# Sheet1.net
KiCad netlist of a schematic drawn in Altium Designer
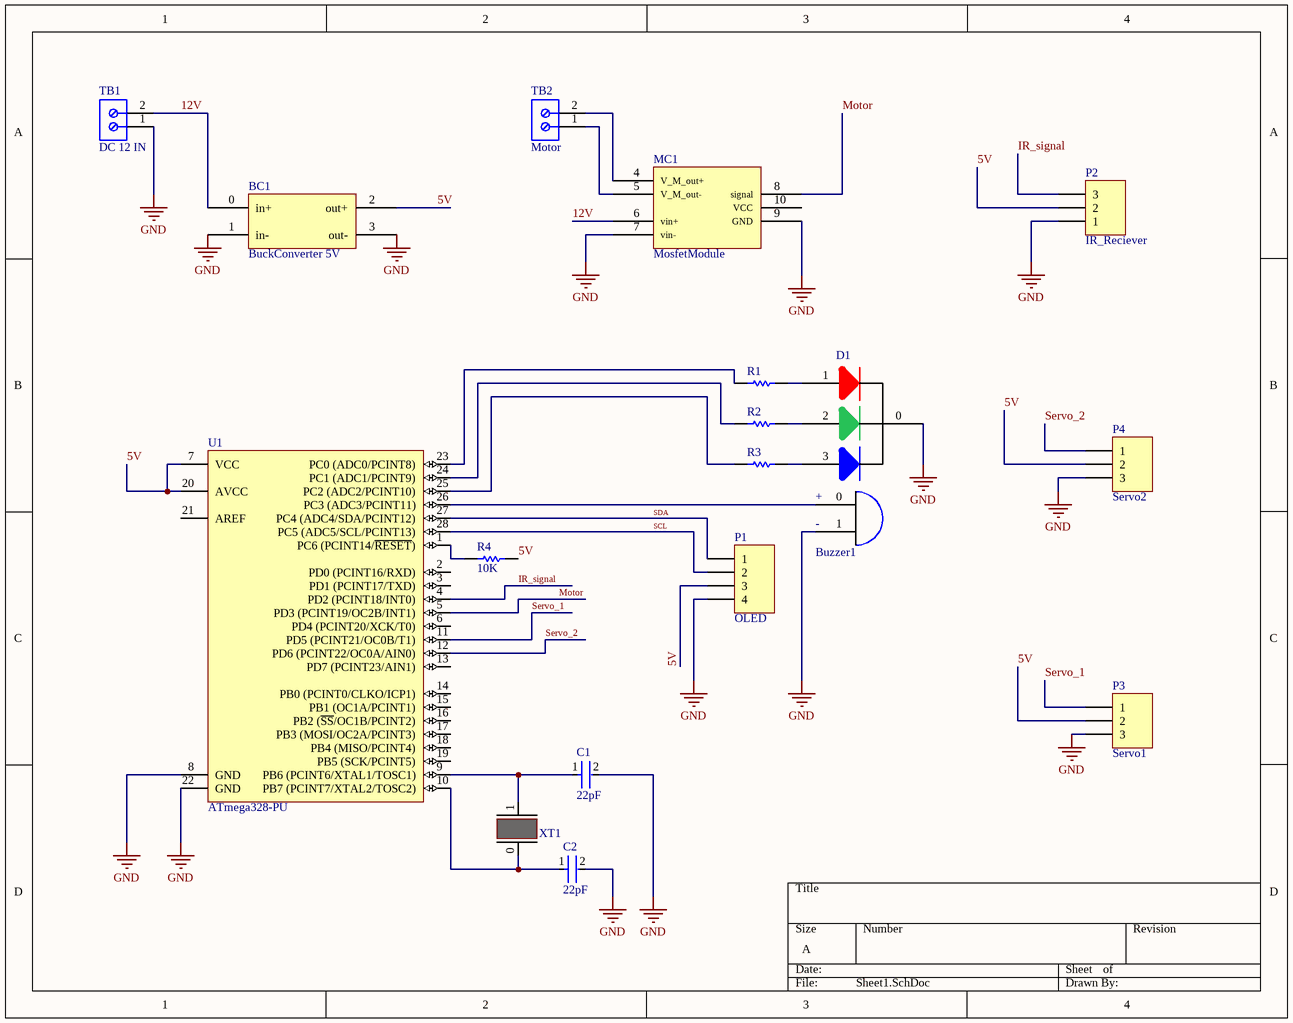
[diagram p0: Sheet1.SchDoc]

(export (version "E")
  (design (tool "Eeschema 10.0.6"))
  (components
    (comp (ref "BC1")
      (value "BuckConverter 5V")
      (footprint "BUCK")
      (libsource (lib "Schlib1") (part "BuckConverter"))
    )
    (comp (ref "Buzzer1") (value "Buzzer") (footprint "Buzzer") (libsource (lib "Schlib1") (part "Buzzer")))
    (comp (ref "C1")
      (value "22pF")
      (footprint "FP-RDE0M1-MFG")
      (description "Ceramic Capacitor 100nF ±10% 50V X7R Radial")
      (fields (field (name "TOLERANCE") "10%"))
      (libsource (lib "Altium Content Vault") (part "b4654b650e69147ec39a6b967a45e02"))
    )
    (comp (ref "C2")
      (value "22pF")
      (footprint "FP-RDE0M1-MFG")
      (description "Ceramic Capacitor 100nF ±10% 50V X7R Radial")
      (fields (field (name "TOLERANCE") "10%"))
      (libsource (lib "Altium Content Vault") (part "b4654b650e69147ec39a6b967a45e02"))
    )
    (comp (ref "D1")
      (value "check foot print and real model")
      (footprint "RGB_LED")
      (libsource (lib "Schlib1") (part "RGB_LED"))
    )
    (comp (ref "MC1")
      (value "MosfetModule")
      (footprint "MosfetMoterDriver")
      (libsource (lib "Schlib1") (part "MosfetModule"))
    )
    (comp (ref "P1")
      (value "OLED")
      (footprint "HDR1X4")
      (description "Header, 4-Pin")
      (fields (field (name "PUBLISHER") "Altium Limited"))
      (libsource (lib "Miscellaneous Connectors") (part "Header 4"))
    )
    (comp (ref "P2")
      (value "IR_Reciever")
      (footprint "HDR1X3")
      (description "Header, 3-Pin")
      (fields (field (name "PUBLISHER") "Altium Limited"))
      (libsource (lib "Miscellaneous Connectors") (part "Header 3"))
    )
    (comp (ref "P3")
      (value "Servo1")
      (footprint "HDR1X3")
      (description "Header, 3-Pin")
      (fields (field (name "PUBLISHER") "Altium Limited"))
      (libsource (lib "") (part "Header 3_1"))
    )
    (comp (ref "P4")
      (value "Servo2")
      (footprint "HDR1X3")
      (description "Header, 3-Pin")
      (fields (field (name "PUBLISHER") "Altium Limited"))
      (libsource (lib "") (part "Header 3_1"))
    )
    (comp (ref "R1")
      (value "MFR-25FBF52-1K")
      (footprint "RESA60-630X240")
      (description "Axial Resistor, 1 KOhm, +/- 1%, 250 mW, -55 to 155 degC, 2-Pin THD, RoHS, Bulk")
      (fields (field (name "TOLERANCE") "1%"))
      (libsource (lib "Altium Content Vault") (part "RES-2"))
    )
    (comp (ref "R2")
      (value "MFR-25FBF52-1K")
      (footprint "RESA60-630X240")
      (description "Axial Resistor, 1 KOhm, +/- 1%, 250 mW, -55 to 155 degC, 2-Pin THD, RoHS, Bulk")
      (fields (field (name "TOLERANCE") "1%"))
      (libsource (lib "Altium Content Vault") (part "RES-2"))
    )
    (comp (ref "R3")
      (value "MFR-25FBF52-1K")
      (footprint "RESA60-630X240")
      (description "Axial Resistor, 1 KOhm, +/- 1%, 250 mW, -55 to 155 degC, 2-Pin THD, RoHS, Bulk")
      (fields (field (name "TOLERANCE") "1%"))
      (libsource (lib "Altium Content Vault") (part "RES-2"))
    )
    (comp (ref "R4")
      (value "10K")
      (footprint "RESA60-630X240")
      (description "Axial Resistor, 1 KOhm, +/- 1%, 250 mW, -55 to 155 degC, 2-Pin THD, RoHS, Bulk")
      (fields (field (name "TOLERANCE") "1%"))
      (libsource (lib "Altium Content Vault") (part "RES-2"))
    )
    (comp (ref "TB1")
      (value "DC 12 IN")
      (footprint "Terminal Block")
      (libsource (lib "Schlib1") (part "Terminal Block"))
    )
    (comp (ref "TB2")
      (value "Motor")
      (footprint "Terminal Block")
      (libsource (lib "Schlib1") (part "Terminal Block"))
    )
    (comp (ref "U1")
      (value "ATmega328-PU")
      (footprint "28P3")
      (libsource (lib "Altium Content Vault") (part "MC-8B-ATM48-IL28"))
    )
    (comp (ref "XT1")
      (value "Crystal Oscillator")
      (footprint "CrystalOscillator")
      (libsource (lib "Schlib1") (part "Crystal Oscillator"))
    )
  )
  (nets
    (net (code "1") (name "/5V") (class "Default")
      (node (ref "BC1") (pin "2") (pinfunction "out+_2") (pintype "passive"))
      (node (ref "P1") (pin "3") (pinfunction "3_3") (pintype "passive"))
      (node (ref "P2") (pin "2") (pinfunction "2_2") (pintype "passive"))
      (node (ref "P3") (pin "2") (pinfunction "2_2") (pintype "passive"))
      (node (ref "P4") (pin "2") (pinfunction "2_2") (pintype "passive"))
      (node (ref "R4") (pin "2") (pinfunction "2_2") (pintype "passive"))
      (node (ref "U1") (pin "20") (pinfunction "AVCC_20") (pintype "power_in"))
      (node (ref "U1") (pin "7") (pinfunction "VCC_7") (pintype "power_in"))
    )
    (net (code "2") (name "/12V") (class "Default")
      (node (ref "BC1") (pin "0") (pinfunction "in+_0") (pintype "passive"))
      (node (ref "MC1") (pin "6") (pinfunction "vin+_6") (pintype "passive"))
      (node (ref "TB1") (pin "2") (pinfunction "2_2") (pintype "passive"))
    )
    (net (code "3") (name "/IR_signal") (class "Default")
      (node (ref "P2") (pin "3") (pinfunction "3_3") (pintype "passive"))
      (node (ref "U1") (pin "4") (pinfunction "PD2_(PCINT18/INT0)_4") (pintype "bidirectional"))
    )
    (net (code "4") (name "/Motor") (class "Default")
      (node (ref "MC1") (pin "8") (pinfunction "signal_8") (pintype "passive"))
      (node (ref "U1") (pin "5") (pinfunction "PD3_(PCINT19/OC2B/INT1)_5") (pintype "bidirectional"))
    )
    (net (code "5") (name "/SCL") (class "Default")
      (node (ref "P1") (pin "2") (pinfunction "2_2") (pintype "passive"))
      (node (ref "U1") (pin "28") (pinfunction "PC5_(ADC5/SCL/PCINT13)_28") (pintype "bidirectional"))
    )
    (net (code "6") (name "/SDA") (class "Default")
      (node (ref "P1") (pin "1") (pinfunction "1_1") (pintype "passive"))
      (node (ref "U1") (pin "27") (pinfunction "PC4_(ADC4/SDA/PCINT12)_27") (pintype "bidirectional"))
    )
    (net (code "7") (name "/Servo_1") (class "Default")
      (node (ref "P3") (pin "1") (pinfunction "1_1") (pintype "passive"))
      (node (ref "U1") (pin "11") (pinfunction "PD5_(PCINT21/OC0B/T1)_11") (pintype "bidirectional"))
    )
    (net (code "8") (name "/Servo_2") (class "Default")
      (node (ref "P4") (pin "1") (pinfunction "1_1") (pintype "passive"))
      (node (ref "U1") (pin "12") (pinfunction "PD6_(PCINT22/OC0A/AIN0)_12") (pintype "bidirectional"))
    )
    (net (code "9") (name "GND") (class "Default")
      (node (ref "BC1") (pin "1") (pinfunction "in-_1") (pintype "passive"))
      (node (ref "BC1") (pin "3") (pinfunction "out-_3") (pintype "passive"))
      (node (ref "Buzzer1") (pin "1") (pinfunction "16_1") (pintype "passive"))
      (node (ref "C1") (pin "2") (pinfunction "2_2") (pintype "passive"))
      (node (ref "C2") (pin "2") (pinfunction "2_2") (pintype "passive"))
      (node (ref "D1") (pin "0") (pinfunction "14_0") (pintype "passive"))
      (node (ref "MC1") (pin "7") (pinfunction "vin-_7") (pintype "passive"))
      (node (ref "MC1") (pin "9") (pinfunction "GND_9") (pintype "passive"))
      (node (ref "P1") (pin "4") (pinfunction "4_4") (pintype "passive"))
      (node (ref "P2") (pin "1") (pinfunction "1_1") (pintype "passive"))
      (node (ref "P3") (pin "3") (pinfunction "3_3") (pintype "passive"))
      (node (ref "P4") (pin "3") (pinfunction "3_3") (pintype "passive"))
      (node (ref "TB1") (pin "1") (pinfunction "1_1") (pintype "passive"))
      (node (ref "U1") (pin "22") (pinfunction "GND_22") (pintype "power_in"))
      (node (ref "U1") (pin "8") (pinfunction "GND_8") (pintype "power_in"))
    )
    (net (code "10") (name "Net-(Buzzer1-15)") (class "Default")
      (node (ref "Buzzer1") (pin "0") (pinfunction "15_0") (pintype "passive"))
      (node (ref "U1") (pin "26") (pinfunction "PC3_(ADC3/PCINT11)_26") (pintype "bidirectional"))
    )
    (net (code "11") (name "Net-(D1-11)") (class "Default")
      (node (ref "D1") (pin "1") (pinfunction "11_1") (pintype "passive"))
      (node (ref "R1") (pin "2") (pinfunction "2_2") (pintype "passive"))
    )
    (net (code "12") (name "Net-(D1-12)") (class "Default")
      (node (ref "D1") (pin "2") (pinfunction "12_2") (pintype "passive"))
      (node (ref "R2") (pin "2") (pinfunction "2_2") (pintype "passive"))
    )
    (net (code "13") (name "Net-(D1-13)") (class "Default")
      (node (ref "D1") (pin "3") (pinfunction "13_3") (pintype "passive"))
      (node (ref "R3") (pin "2") (pinfunction "2_2") (pintype "passive"))
    )
    (net (code "14") (name "Net-(MC1-V_M_out+)") (class "Default")
      (node (ref "MC1") (pin "4") (pinfunction "V_M_out+_4") (pintype "passive"))
      (node (ref "TB2") (pin "2") (pinfunction "2_2") (pintype "passive"))
    )
    (net (code "15") (name "Net-(MC1-V_M_out-)") (class "Default")
      (node (ref "MC1") (pin "5") (pinfunction "V_M_out-_5") (pintype "passive"))
      (node (ref "TB2") (pin "1") (pinfunction "1_1") (pintype "passive"))
    )
    (net (code "16") (name "Net-(U1-PB6_(PCINT6{slash}XTAL1{slash}TOSC1))") (class "Default")
      (node (ref "C1") (pin "1") (pinfunction "1_1") (pintype "passive"))
      (node (ref "U1") (pin "9") (pinfunction "PB6_(PCINT6/XTAL1/TOSC1)_9") (pintype "bidirectional"))
      (node (ref "XT1") (pin "1") (pinfunction "18_1") (pintype "passive"))
    )
    (net (code "17") (name "Net-(U1-PB7_(PCINT7{slash}XTAL2{slash}TOSC2))") (class "Default")
      (node (ref "C2") (pin "1") (pinfunction "1_1") (pintype "passive"))
      (node (ref "U1") (pin "10") (pinfunction "PB7_(PCINT7/XTAL2/TOSC2)_10") (pintype "bidirectional"))
      (node (ref "XT1") (pin "0") (pinfunction "17_0") (pintype "passive"))
    )
    (net (code "18") (name "Net-(U1-PC0_(ADC0{slash}PCINT8))") (class "Default")
      (node (ref "R1") (pin "1") (pinfunction "1_1") (pintype "passive"))
      (node (ref "U1") (pin "23") (pinfunction "PC0_(ADC0/PCINT8)_23") (pintype "bidirectional"))
    )
    (net (code "19") (name "Net-(U1-PC1_(ADC1{slash}PCINT9))") (class "Default")
      (node (ref "R2") (pin "1") (pinfunction "1_1") (pintype "passive"))
      (node (ref "U1") (pin "24") (pinfunction "PC1_(ADC1/PCINT9)_24") (pintype "bidirectional"))
    )
    (net (code "20") (name "Net-(U1-PC2_(ADC2{slash}PCINT10))") (class "Default")
      (node (ref "R3") (pin "1") (pinfunction "1_1") (pintype "passive"))
      (node (ref "U1") (pin "25") (pinfunction "PC2_(ADC2/PCINT10)_25") (pintype "bidirectional"))
    )
    (net (code "21") (name "Net-(U1-PC6_(PCINT14{slash}~{RESET}))") (class "Default")
      (node (ref "R4") (pin "1") (pinfunction "1_1") (pintype "passive"))
      (node (ref "U1") (pin "1") (pinfunction "PC6_(PCINT14/~{RESET})_1") (pintype "bidirectional"))
    )
    (net (code "22") (name "unconnected-(MC1-VCC-Pad10)") (class "Default")
      (node (ref "MC1") (pin "10") (pinfunction "VCC_10") (pintype "passive"))
    )
    (net (code "23") (name "unconnected-(U1-AREF-Pad21)") (class "Default")
      (node (ref "U1") (pin "21") (pinfunction "AREF_21") (pintype "power_in"))
    )
    (net (code "24") (name "unconnected-(U1-PB0_(PCINT0{slash}CLKO{slash}ICP1)-Pad14)") (class "Default")
      (node (ref "U1") (pin "14") (pinfunction "PB0_(PCINT0/CLKO/ICP1)_14") (pintype "bidirectional"))
    )
    (net (code "25") (name "unconnected-(U1-PB1_(OC1A{slash}PCINT1)-Pad15)") (class "Default")
      (node (ref "U1") (pin "15") (pinfunction "PB1_(OC1A/PCINT1)_15") (pintype "bidirectional"))
    )
    (net (code "26") (name "unconnected-(U1-PB2_(~{SS}{slash}OC1B{slash}PCINT2)-Pad16)") (class "Default")
      (node (ref "U1") (pin "16") (pinfunction "PB2_(~{SS}/OC1B/PCINT2)_16") (pintype "bidirectional"))
    )
    (net (code "27") (name "unconnected-(U1-PB3_(MOSI{slash}OC2A{slash}PCINT3)-Pad17)") (class "Default")
      (node (ref "U1") (pin "17") (pinfunction "PB3_(MOSI/OC2A/PCINT3)_17") (pintype "bidirectional"))
    )
    (net (code "28") (name "unconnected-(U1-PB4_(MISO{slash}PCINT4)-Pad18)") (class "Default")
      (node (ref "U1") (pin "18") (pinfunction "PB4_(MISO/PCINT4)_18") (pintype "bidirectional"))
    )
    (net (code "29") (name "unconnected-(U1-PB5_(SCK{slash}PCINT5)-Pad19)") (class "Default")
      (node (ref "U1") (pin "19") (pinfunction "PB5_(SCK/PCINT5)_19") (pintype "bidirectional"))
    )
    (net (code "30") (name "unconnected-(U1-PD0_(PCINT16{slash}RXD)-Pad2)") (class "Default")
      (node (ref "U1") (pin "2") (pinfunction "PD0_(PCINT16/RXD)_2") (pintype "bidirectional"))
    )
    (net (code "31") (name "unconnected-(U1-PD1_(PCINT17{slash}TXD)-Pad3)") (class "Default")
      (node (ref "U1") (pin "3") (pinfunction "PD1_(PCINT17/TXD)_3") (pintype "bidirectional"))
    )
    (net (code "32") (name "unconnected-(U1-PD4_(PCINT20{slash}XCK{slash}T0)-Pad6)") (class "Default")
      (node (ref "U1") (pin "6") (pinfunction "PD4_(PCINT20/XCK/T0)_6") (pintype "bidirectional"))
    )
    (net (code "33") (name "unconnected-(U1-PD7_(PCINT23{slash}AIN1)-Pad13)") (class "Default")
      (node (ref "U1") (pin "13") (pinfunction "PD7_(PCINT23/AIN1)_13") (pintype "bidirectional"))
    )
  )
)
